# Daughter_Board_V3.net
KiCad netlist of a schematic drawn in EAGLE
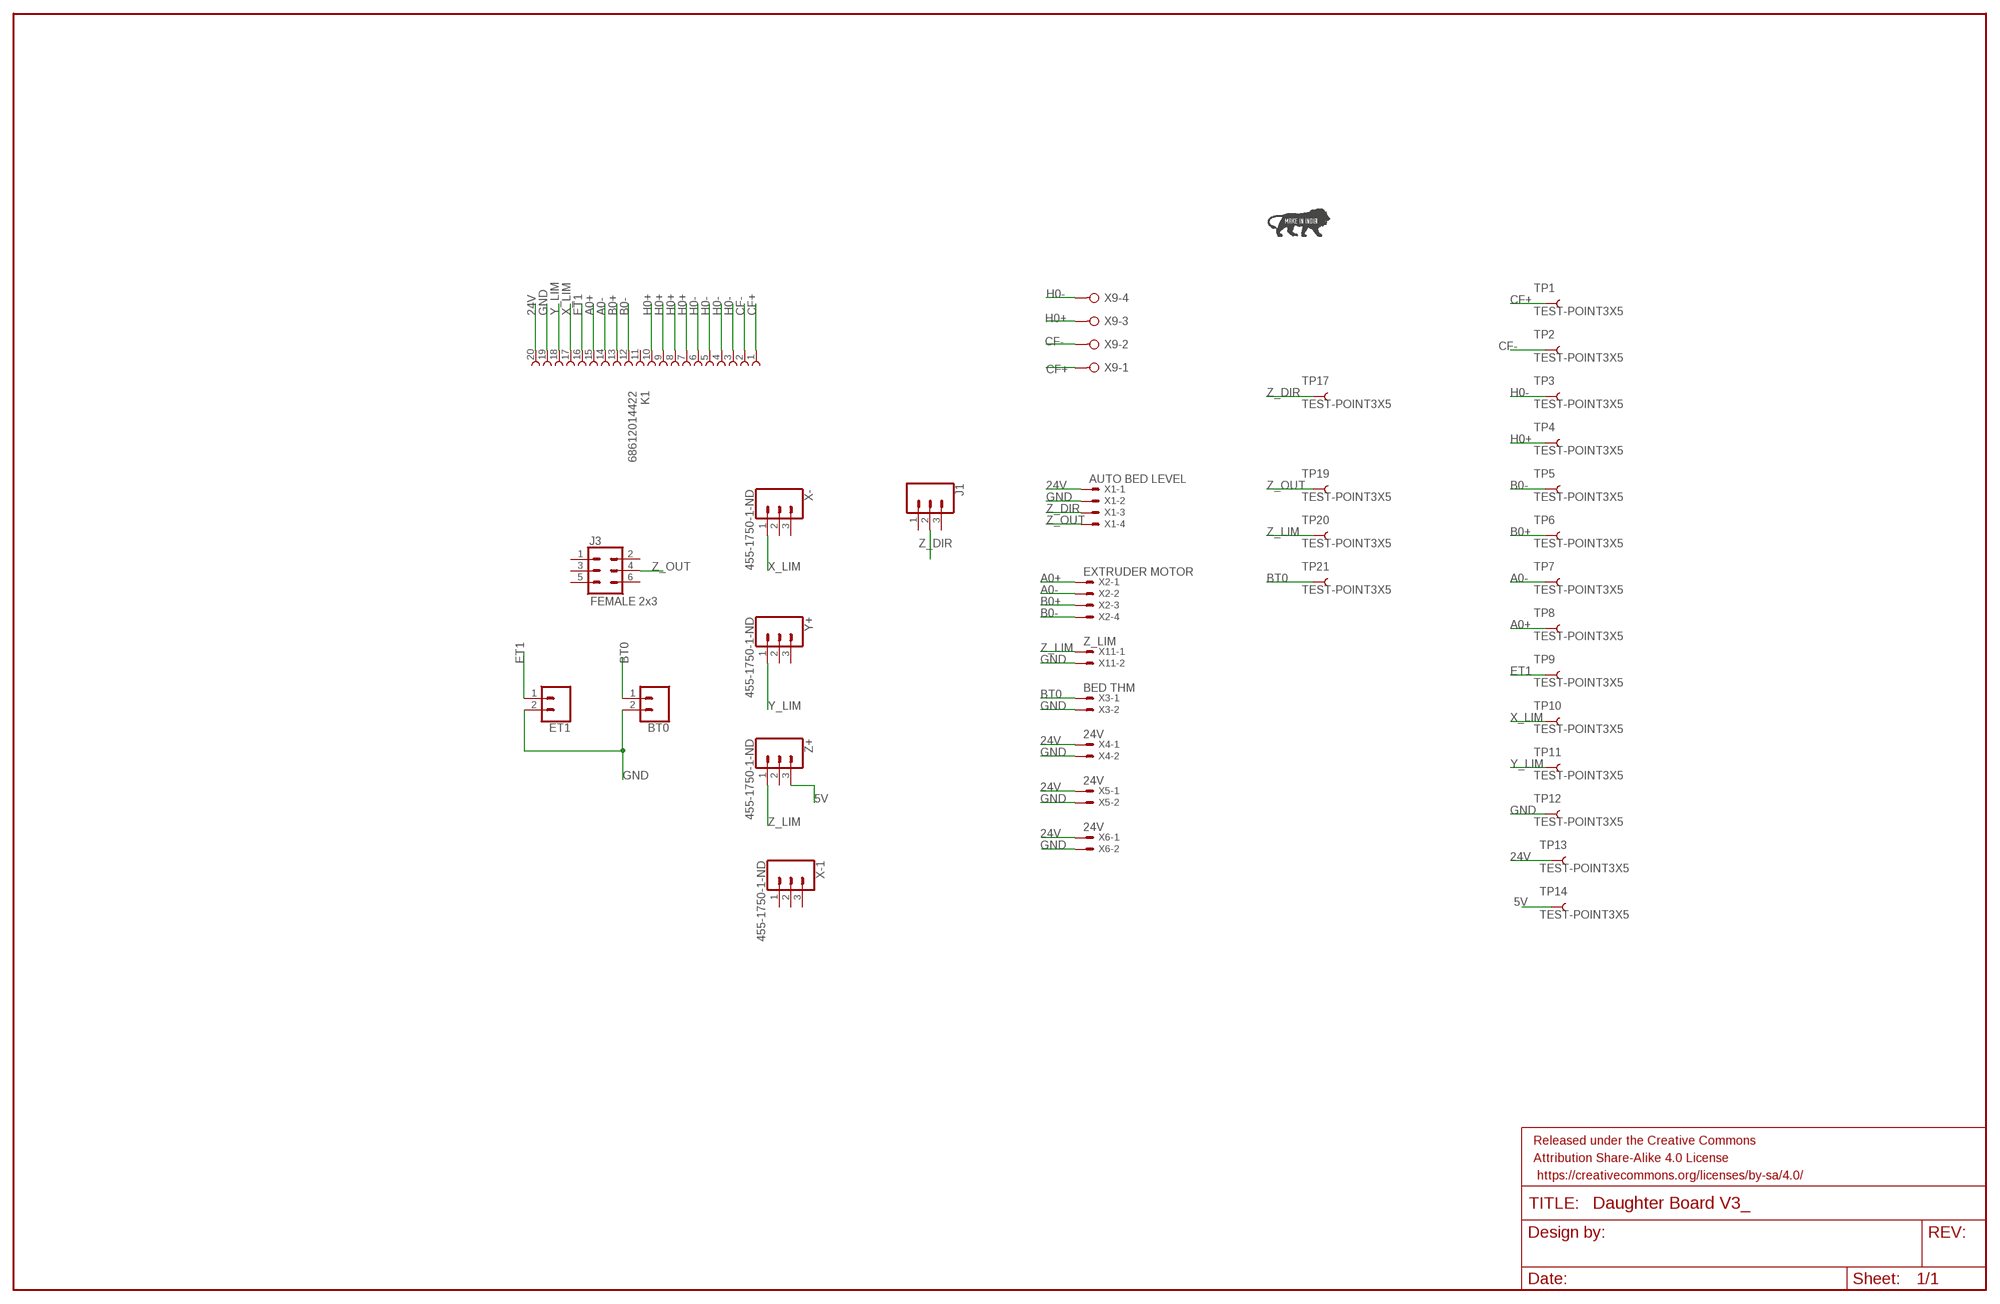
[diagram p0: schematic, sheet 1]

(export (version "E")
  (design (tool "Eeschema 10.0.6"))
  (components
    (comp (ref "BT0")
      (value "CONN_02")
      (footprint "eagle-import:1X02")
      (libsource (lib "eagle-import") (part "CONN_02"))
    )
    (comp (ref "ET1")
      (value "CONN_02")
      (footprint "eagle-import:1X02")
      (libsource (lib "eagle-import") (part "CONN_02"))
    )
    (comp (ref "FRAME1")
      (value "FRAME-LEDGER")
      (footprint "eagle-import:CREATIVE_COMMONS")
      (libsource (lib "eagle-import") (part "FRAME-LEDGER"))
    )
    (comp (ref "J1")
      (value "455-1750-1-ND")
      (footprint "eagle-import:1X03")
      (libsource (lib "eagle-import") (part "CONN_03"))
    )
    (comp (ref "J3")
      (value "FEMALE 2x3")
      (footprint "eagle-import:2X3")
      (libsource (lib "eagle-import") (part "CONN_03X2FEMALE"))
    )
    (comp (ref "K1")
      (value "68612014422")
      (footprint "eagle-import:68612014422")
      (libsource (lib "eagle-import") (part "68612014422"))
    )
    (comp (ref "TP1")
      (value "TEST-POINT3X5")
      (footprint "eagle-import:PAD.03X.05")
      (libsource (lib "eagle-import") (part "TEST-POINT3X5"))
    )
    (comp (ref "TP2")
      (value "TEST-POINT3X5")
      (footprint "eagle-import:PAD.03X.05")
      (libsource (lib "eagle-import") (part "TEST-POINT3X5"))
    )
    (comp (ref "TP3")
      (value "TEST-POINT3X5")
      (footprint "eagle-import:PAD.03X.05")
      (libsource (lib "eagle-import") (part "TEST-POINT3X5"))
    )
    (comp (ref "TP4")
      (value "TEST-POINT3X5")
      (footprint "eagle-import:PAD.03X.05")
      (libsource (lib "eagle-import") (part "TEST-POINT3X5"))
    )
    (comp (ref "TP5")
      (value "TEST-POINT3X5")
      (footprint "eagle-import:PAD.03X.05")
      (libsource (lib "eagle-import") (part "TEST-POINT3X5"))
    )
    (comp (ref "TP6")
      (value "TEST-POINT3X5")
      (footprint "eagle-import:PAD.03X.05")
      (libsource (lib "eagle-import") (part "TEST-POINT3X5"))
    )
    (comp (ref "TP7")
      (value "TEST-POINT3X5")
      (footprint "eagle-import:PAD.03X.05")
      (libsource (lib "eagle-import") (part "TEST-POINT3X5"))
    )
    (comp (ref "TP8")
      (value "TEST-POINT3X5")
      (footprint "eagle-import:PAD.03X.05")
      (libsource (lib "eagle-import") (part "TEST-POINT3X5"))
    )
    (comp (ref "TP9")
      (value "TEST-POINT3X5")
      (footprint "eagle-import:PAD.03X.05")
      (libsource (lib "eagle-import") (part "TEST-POINT3X5"))
    )
    (comp (ref "TP10")
      (value "TEST-POINT3X5")
      (footprint "eagle-import:PAD.03X.05")
      (libsource (lib "eagle-import") (part "TEST-POINT3X5"))
    )
    (comp (ref "TP11")
      (value "TEST-POINT3X5")
      (footprint "eagle-import:PAD.03X.05")
      (libsource (lib "eagle-import") (part "TEST-POINT3X5"))
    )
    (comp (ref "TP12")
      (value "TEST-POINT3X5")
      (footprint "eagle-import:PAD.03X.05")
      (libsource (lib "eagle-import") (part "TEST-POINT3X5"))
    )
    (comp (ref "TP13")
      (value "TEST-POINT3X5")
      (footprint "eagle-import:PAD.03X.05")
      (libsource (lib "eagle-import") (part "TEST-POINT3X5"))
    )
    (comp (ref "TP14")
      (value "TEST-POINT3X5")
      (footprint "eagle-import:PAD.03X.05")
      (libsource (lib "eagle-import") (part "TEST-POINT3X5"))
    )
    (comp (ref "TP17")
      (value "TEST-POINT3X5")
      (footprint "eagle-import:PAD.03X.05")
      (libsource (lib "eagle-import") (part "TEST-POINT3X5"))
    )
    (comp (ref "TP19")
      (value "TEST-POINT3X5")
      (footprint "eagle-import:PAD.03X.05")
      (libsource (lib "eagle-import") (part "TEST-POINT3X5"))
    )
    (comp (ref "TP20")
      (value "TEST-POINT3X5")
      (footprint "eagle-import:PAD.03X.05")
      (libsource (lib "eagle-import") (part "TEST-POINT3X5"))
    )
    (comp (ref "TP21")
      (value "TEST-POINT3X5")
      (footprint "eagle-import:PAD.03X.05")
      (libsource (lib "eagle-import") (part "TEST-POINT3X5"))
    )
    (comp (ref "U$2")
      (value "MAKEININDIA")
      (footprint "eagle-import:MAKEININDIA")
      (libsource (lib "eagle-import") (part "MAKEININDIA"))
    )
    (comp (ref "X-")
      (value "455-1750-1-ND")
      (footprint "eagle-import:1X03")
      (libsource (lib "eagle-import") (part "CONN_03"))
    )
    (comp (ref "X-1")
      (value "455-1750-1-ND")
      (footprint "eagle-import:1X03")
      (libsource (lib "eagle-import") (part "CONN_03"))
    )
    (comp (ref "X1")
      (value "AUTO BED LEVEL")
      (footprint "eagle-import:JST-XH-04-PACKAGE-LONG-PAD")
      (libsource (lib "eagle-import") (part "JST-XH-04-PIN-LONG-PAD"))
    )
    (comp (ref "X2")
      (value "EXTRUDER MOTOR")
      (footprint "eagle-import:JST-XH-04-PACKAGE-LONG-PAD")
      (libsource (lib "eagle-import") (part "JST-XH-04-PIN-LONG-PAD"))
    )
    (comp (ref "X3")
      (value "BED THM")
      (footprint "eagle-import:JST-XH-02-PACKAGE-LONG-PAD")
      (libsource (lib "eagle-import") (part "JST-XH-02-PIN-LONG-PAD"))
    )
    (comp (ref "X4")
      (value "24V")
      (footprint "eagle-import:JST-XH-02-PACKAGE-LONG-PAD")
      (libsource (lib "eagle-import") (part "JST-XH-02-PIN-LONG-PAD"))
    )
    (comp (ref "X5")
      (value "24V")
      (footprint "eagle-import:JST-XH-02-PACKAGE-LONG-PAD")
      (libsource (lib "eagle-import") (part "JST-XH-02-PIN-LONG-PAD"))
    )
    (comp (ref "X6")
      (value "24V")
      (footprint "eagle-import:JST-XH-02-PACKAGE-LONG-PAD")
      (libsource (lib "eagle-import") (part "JST-XH-02-PIN-LONG-PAD"))
    )
    (comp (ref "X9")
      (value "W237-04P")
      (footprint "eagle-import:W237-4P")
      (libsource (lib "eagle-import") (part "W237-04P"))
    )
    (comp (ref "X11")
      (value "Z_LIM")
      (footprint "eagle-import:JST-XH-02-PACKAGE-LONG-PAD")
      (libsource (lib "eagle-import") (part "JST-XH-02-PIN-LONG-PAD"))
    )
    (comp (ref "Y+")
      (value "455-1750-1-ND")
      (footprint "eagle-import:1X03")
      (libsource (lib "eagle-import") (part "CONN_03"))
    )
    (comp (ref "Z+")
      (value "455-1750-1-ND")
      (footprint "eagle-import:1X03")
      (libsource (lib "eagle-import") (part "CONN_03"))
    )
  )
  (nets
    (net (code "1") (name "/5V") (class "Default")
      (node (ref "TP14") (pin "P$1") (pinfunction "1_P$1") (pintype "bidirectional"))
      (node (ref "Z+") (pin "3") (pinfunction "3_3") (pintype "passive"))
    )
    (net (code "2") (name "/24V") (class "Default")
      (node (ref "K1") (pin "20") (pinfunction "20_20") (pintype "passive"))
      (node (ref "TP13") (pin "P$1") (pinfunction "1_P$1") (pintype "bidirectional"))
      (node (ref "X1") (pin "1") (pinfunction "S_1") (pintype "passive"))
      (node (ref "X4") (pin "1") (pinfunction "S_1") (pintype "passive"))
      (node (ref "X5") (pin "1") (pinfunction "S_1") (pintype "passive"))
      (node (ref "X6") (pin "1") (pinfunction "S_1") (pintype "passive"))
    )
    (net (code "3") (name "/A0+") (class "Default")
      (node (ref "K1") (pin "15") (pinfunction "15_15") (pintype "passive"))
      (node (ref "TP8") (pin "P$1") (pinfunction "1_P$1") (pintype "bidirectional"))
      (node (ref "X2") (pin "1") (pinfunction "S_1") (pintype "passive"))
    )
    (net (code "4") (name "/A0-") (class "Default")
      (node (ref "K1") (pin "14") (pinfunction "14_14") (pintype "passive"))
      (node (ref "TP7") (pin "P$1") (pinfunction "1_P$1") (pintype "bidirectional"))
      (node (ref "X2") (pin "2") (pinfunction "S_2") (pintype "passive"))
    )
    (net (code "5") (name "/B0+") (class "Default")
      (node (ref "K1") (pin "13") (pinfunction "13_13") (pintype "passive"))
      (node (ref "TP6") (pin "P$1") (pinfunction "1_P$1") (pintype "bidirectional"))
      (node (ref "X2") (pin "3") (pinfunction "S_3") (pintype "passive"))
    )
    (net (code "6") (name "/B0-") (class "Default")
      (node (ref "K1") (pin "12") (pinfunction "12_12") (pintype "passive"))
      (node (ref "TP5") (pin "P$1") (pinfunction "1_P$1") (pintype "bidirectional"))
      (node (ref "X2") (pin "4") (pinfunction "S_4") (pintype "passive"))
    )
    (net (code "7") (name "/BT0") (class "Default")
      (node (ref "BT0") (pin "1") (pinfunction "1_1") (pintype "passive"))
      (node (ref "TP21") (pin "P$1") (pinfunction "1_P$1") (pintype "bidirectional"))
      (node (ref "X3") (pin "1") (pinfunction "S_1") (pintype "passive"))
    )
    (net (code "8") (name "/CF+") (class "Default")
      (node (ref "K1") (pin "1") (pinfunction "1_1") (pintype "passive"))
      (node (ref "TP1") (pin "P$1") (pinfunction "1_P$1") (pintype "bidirectional"))
      (node (ref "X9") (pin "1") (pinfunction "KL_1") (pintype "passive"))
    )
    (net (code "9") (name "/CF-") (class "Default")
      (node (ref "K1") (pin "2") (pinfunction "2_2") (pintype "passive"))
      (node (ref "TP2") (pin "P$1") (pinfunction "1_P$1") (pintype "bidirectional"))
      (node (ref "X9") (pin "2") (pinfunction "KL_2") (pintype "passive"))
    )
    (net (code "10") (name "/ET1") (class "Default")
      (node (ref "ET1") (pin "1") (pinfunction "1_1") (pintype "passive"))
      (node (ref "K1") (pin "16") (pinfunction "16_16") (pintype "passive"))
      (node (ref "TP9") (pin "P$1") (pinfunction "1_P$1") (pintype "bidirectional"))
    )
    (net (code "11") (name "/GND") (class "Default")
      (node (ref "BT0") (pin "2") (pinfunction "2_2") (pintype "passive"))
      (node (ref "ET1") (pin "2") (pinfunction "2_2") (pintype "passive"))
      (node (ref "K1") (pin "19") (pinfunction "19_19") (pintype "passive"))
      (node (ref "TP12") (pin "P$1") (pinfunction "1_P$1") (pintype "bidirectional"))
      (node (ref "X1") (pin "2") (pinfunction "S_2") (pintype "passive"))
      (node (ref "X11") (pin "2") (pinfunction "S_2") (pintype "passive"))
      (node (ref "X3") (pin "2") (pinfunction "S_2") (pintype "passive"))
      (node (ref "X4") (pin "2") (pinfunction "S_2") (pintype "passive"))
      (node (ref "X5") (pin "2") (pinfunction "S_2") (pintype "passive"))
      (node (ref "X6") (pin "2") (pinfunction "S_2") (pintype "passive"))
    )
    (net (code "12") (name "/H0+") (class "Default")
      (node (ref "K1") (pin "10") (pinfunction "10_10") (pintype "passive"))
      (node (ref "K1") (pin "7") (pinfunction "7_7") (pintype "passive"))
      (node (ref "K1") (pin "8") (pinfunction "8_8") (pintype "passive"))
      (node (ref "K1") (pin "9") (pinfunction "9_9") (pintype "passive"))
      (node (ref "TP4") (pin "P$1") (pinfunction "1_P$1") (pintype "bidirectional"))
      (node (ref "X9") (pin "3") (pinfunction "KL_3") (pintype "passive"))
    )
    (net (code "13") (name "/H0-") (class "Default")
      (node (ref "K1") (pin "3") (pinfunction "3_3") (pintype "passive"))
      (node (ref "K1") (pin "4") (pinfunction "4_4") (pintype "passive"))
      (node (ref "K1") (pin "5") (pinfunction "5_5") (pintype "passive"))
      (node (ref "K1") (pin "6") (pinfunction "6_6") (pintype "passive"))
      (node (ref "TP3") (pin "P$1") (pinfunction "1_P$1") (pintype "bidirectional"))
      (node (ref "X9") (pin "4") (pinfunction "KL_4") (pintype "passive"))
    )
    (net (code "14") (name "/X_LIM") (class "Default")
      (node (ref "K1") (pin "17") (pinfunction "17_17") (pintype "passive"))
      (node (ref "TP10") (pin "P$1") (pinfunction "1_P$1") (pintype "bidirectional"))
      (node (ref "X-") (pin "1") (pinfunction "1_1") (pintype "passive"))
    )
    (net (code "15") (name "/Y_LIM") (class "Default")
      (node (ref "K1") (pin "18") (pinfunction "18_18") (pintype "passive"))
      (node (ref "TP11") (pin "P$1") (pinfunction "1_P$1") (pintype "bidirectional"))
      (node (ref "Y+") (pin "1") (pinfunction "1_1") (pintype "passive"))
    )
    (net (code "16") (name "/Z_DIR") (class "Default")
      (node (ref "J1") (pin "2") (pinfunction "2_2") (pintype "passive"))
      (node (ref "TP17") (pin "P$1") (pinfunction "1_P$1") (pintype "bidirectional"))
      (node (ref "X1") (pin "3") (pinfunction "S_3") (pintype "passive"))
    )
    (net (code "17") (name "/Z_LIM") (class "Default")
      (node (ref "TP20") (pin "P$1") (pinfunction "1_P$1") (pintype "bidirectional"))
      (node (ref "X11") (pin "1") (pinfunction "S_1") (pintype "passive"))
      (node (ref "Z+") (pin "1") (pinfunction "1_1") (pintype "passive"))
    )
    (net (code "18") (name "/Z_OUT") (class "Default")
      (node (ref "J3") (pin "4") (pinfunction "4_4") (pintype "bidirectional"))
      (node (ref "TP19") (pin "P$1") (pinfunction "1_P$1") (pintype "bidirectional"))
      (node (ref "X1") (pin "4") (pinfunction "S_4") (pintype "passive"))
    )
    (net (code "19") (name "unconnected-(J1-Pad1)") (class "Default")
      (node (ref "J1") (pin "1") (pinfunction "1_1") (pintype "passive"))
    )
    (net (code "20") (name "unconnected-(J1-Pad3)") (class "Default")
      (node (ref "J1") (pin "3") (pinfunction "3_3") (pintype "passive"))
    )
    (net (code "21") (name "unconnected-(J3-Pad1)") (class "Default")
      (node (ref "J3") (pin "1") (pinfunction "1_1") (pintype "bidirectional"))
    )
    (net (code "22") (name "unconnected-(J3-Pad2)") (class "Default")
      (node (ref "J3") (pin "2") (pinfunction "2_2") (pintype "bidirectional"))
    )
    (net (code "23") (name "unconnected-(J3-Pad3)") (class "Default")
      (node (ref "J3") (pin "3") (pinfunction "3_3") (pintype "bidirectional"))
    )
    (net (code "24") (name "unconnected-(J3-Pad5)") (class "Default")
      (node (ref "J3") (pin "5") (pinfunction "5_5") (pintype "bidirectional"))
    )
    (net (code "25") (name "unconnected-(J3-Pad6)") (class "Default")
      (node (ref "J3") (pin "6") (pinfunction "6_6") (pintype "bidirectional"))
    )
    (net (code "26") (name "unconnected-(K1-Pad11)") (class "Default")
      (node (ref "K1") (pin "11") (pinfunction "11_11") (pintype "passive"))
    )
    (net (code "27") (name "unconnected-(X--Pad2)") (class "Default")
      (node (ref "X-") (pin "2") (pinfunction "2_2") (pintype "passive"))
    )
    (net (code "28") (name "unconnected-(X--Pad3)") (class "Default")
      (node (ref "X-") (pin "3") (pinfunction "3_3") (pintype "passive"))
    )
    (net (code "29") (name "unconnected-(X-1-Pad1)") (class "Default")
      (node (ref "X-1") (pin "1") (pinfunction "1_1") (pintype "passive"))
    )
    (net (code "30") (name "unconnected-(X-1-Pad2)") (class "Default")
      (node (ref "X-1") (pin "2") (pinfunction "2_2") (pintype "passive"))
    )
    (net (code "31") (name "unconnected-(X-1-Pad3)") (class "Default")
      (node (ref "X-1") (pin "3") (pinfunction "3_3") (pintype "passive"))
    )
    (net (code "32") (name "unconnected-(Y+-Pad2)") (class "Default")
      (node (ref "Y+") (pin "2") (pinfunction "2_2") (pintype "passive"))
    )
    (net (code "33") (name "unconnected-(Y+-Pad3)") (class "Default")
      (node (ref "Y+") (pin "3") (pinfunction "3_3") (pintype "passive"))
    )
    (net (code "34") (name "unconnected-(Z+-Pad2)") (class "Default")
      (node (ref "Z+") (pin "2") (pinfunction "2_2") (pintype "passive"))
    )
  )
)
